# Hall_Sensor.net
KiCad netlist of a schematic drawn in EAGLE
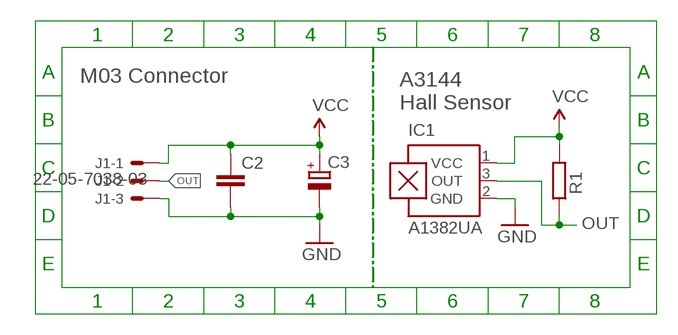
[diagram p0: schematic, sheet 1]

(export (version "E")
  (design (tool "Eeschema 10.0.6"))
  (components
    (comp (ref "C2")
      (value "C-EU025-025X050")
      (footprint "eagle-import:C025-025X050")
      (libsource (lib "eagle-import") (part "C-EU025-025X050"))
    )
    (comp (ref "C3")
      (value "CPOL-EUE2,5-6E")
      (footprint "eagle-import:E2,5-6E")
      (libsource (lib "eagle-import") (part "CPOL-EUE2,5-6E"))
    )
    (comp (ref "IC1")
      (value "A1382UA")
      (footprint "eagle-import:SIP3-UA")
      (fields (field (name "MPN") "A1382LUA-T"))
      (libsource (lib "eagle-import") (part "A13?UA82"))
    )
    (comp (ref "J1")
      (value "22-05-7038-03")
      (footprint "eagle-import:7395-03")
      (fields (field (name "MF") "MOLEX"))
      (libsource (lib "eagle-import") (part "22-?-0305-7038"))
    )
    (comp (ref "R1")
      (value "R-EU_0207/7")
      (footprint "eagle-import:0207_7")
      (libsource (lib "eagle-import") (part "R-EU_0207/7"))
    )
  )
  (nets
    (net (code "1") (name "GND") (class "Default")
      (node (ref "C2") (pin "2") (pinfunction "2_2") (pintype "passive"))
      (node (ref "C3") (pin "-") (pinfunction "-_-") (pintype "passive"))
      (node (ref "IC1") (pin "2") (pinfunction "GND_2") (pintype "power_in"))
      (node (ref "J1") (pin "3") (pinfunction "S_3") (pintype "passive"))
    )
    (net (code "2") (name "OUT") (class "Default")
      (node (ref "IC1") (pin "3") (pinfunction "OUT_3") (pintype "output"))
      (node (ref "J1") (pin "2") (pinfunction "S_2") (pintype "passive"))
      (node (ref "R1") (pin "1") (pinfunction "1_1") (pintype "passive"))
    )
    (net (code "3") (name "VCC") (class "Default")
      (node (ref "C2") (pin "1") (pinfunction "1_1") (pintype "passive"))
      (node (ref "C3") (pin "+") (pinfunction "+_+") (pintype "passive"))
      (node (ref "IC1") (pin "1") (pinfunction "VCC_1") (pintype "power_in"))
      (node (ref "J1") (pin "1") (pinfunction "S_1") (pintype "passive"))
      (node (ref "R1") (pin "2") (pinfunction "2_2") (pintype "passive"))
    )
  )
)
